# Isolated_UART-USB.net
KiCad netlist of a schematic drawn in Altium Designer
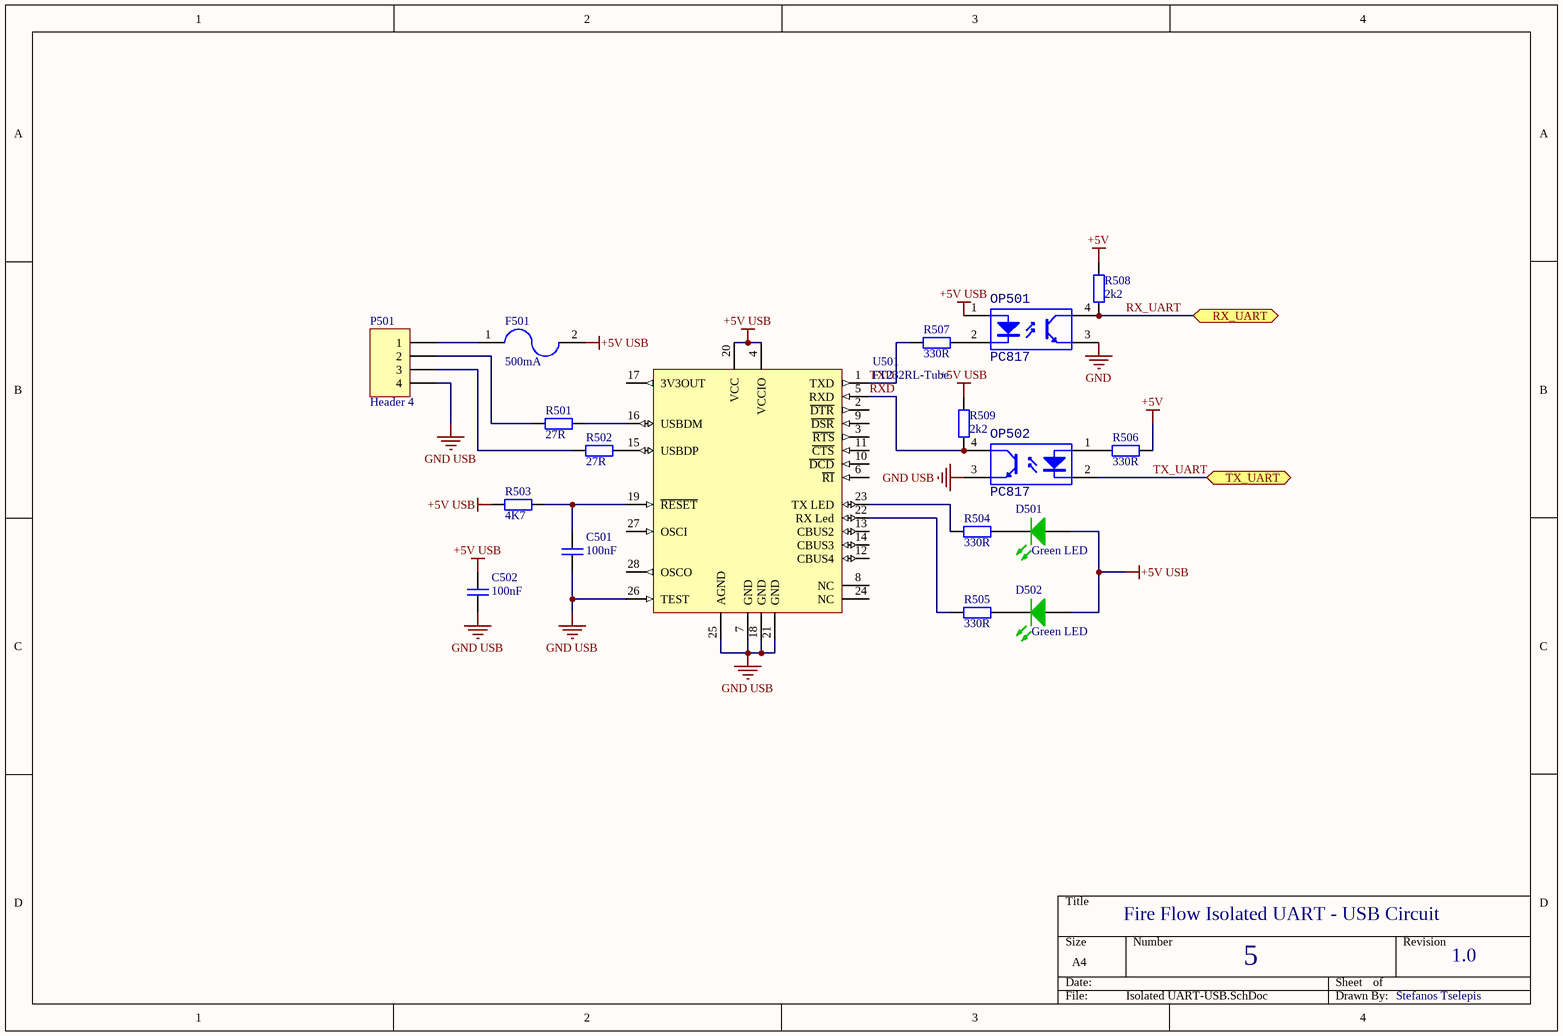
[diagram p0: Isolated UART-USB.SchDoc]

(export (version "E")
  (design (tool "Eeschema 10.0.6"))
  (components
    (comp (ref "C501")
      (value "100nF")
      (footprint "CC2013-0805")
      (libsource (lib "FireFlow Lib") (part "Cap Metal Film"))
    )
    (comp (ref "C502")
      (value "100nF")
      (footprint "CC2013-0805")
      (libsource (lib "FireFlow Lib") (part "Cap Metal Film"))
    )
    (comp (ref "D501")
      (value "Green LED")
      (footprint "CD3216-1206")
      (description "RED")
      (libsource (lib "FireFlow Lib") (part "LED"))
    )
    (comp (ref "D502")
      (value "Green LED")
      (footprint "CD3216-1206")
      (description "RED")
      (libsource (lib "FireFlow Lib") (part "LED"))
    )
    (comp (ref "F501")
      (value "500mA")
      (footprint "CF-1812")
      (description "PPTC")
      (libsource (lib "FireFlow Lib") (part "Fuse"))
    )
    (comp (ref "OP501")
      (value "PC817")
      (footprint "DIP-4")
      (description "DC OPTOCUPLER")
      (libsource (lib "FireFlow") (part "OPTO-DC"))
    )
    (comp (ref "OP502")
      (value "PC817")
      (footprint "DIP-4")
      (description "DC OPTOCUPLER")
      (libsource (lib "FireFlow") (part "OPTO-DC"))
    )
    (comp (ref "P501")
      (value "Header 4")
      (footprint "HDR1X4")
      (description "Header, 4-Pin")
      (fields (field (name "PUBLISHER") "Altium Limited"))
      (libsource (lib "Miscellaneous Connectors") (part "Header 4"))
    )
    (comp (ref "R501") (value "27R") (footprint "CR2012-0805") (libsource (lib "") (part "Resistor_1")))
    (comp (ref "R502") (value "27R") (footprint "CR2012-0805") (libsource (lib "") (part "Resistor_1")))
    (comp (ref "R503")
      (value "4K7")
      (footprint "CR2012-0805")
      (libsource (lib "FireFlow Lib") (part "Resistor"))
    )
    (comp (ref "R504")
      (value "330R")
      (footprint "CR2012-0805")
      (libsource (lib "FireFlow Lib") (part "Resistor"))
    )
    (comp (ref "R505")
      (value "330R")
      (footprint "CR2012-0805")
      (libsource (lib "FireFlow Lib") (part "Resistor"))
    )
    (comp (ref "R506")
      (value "330R")
      (footprint "CR2012-0805")
      (libsource (lib "FireFlow Lib") (part "Resistor"))
    )
    (comp (ref "R507")
      (value "330R")
      (footprint "CR2012-0805")
      (libsource (lib "FireFlow Lib") (part "Resistor"))
    )
    (comp (ref "R508") (value "2k2") (footprint "CR2012-0805") (libsource (lib "") (part "Resistor_2")))
    (comp (ref "R509") (value "2k2") (footprint "CR2012-0805") (libsource (lib "") (part "Resistor_2")))
    (comp (ref "U501")
      (value "FT232RL-Tube")
      (footprint "SSOP-28_N")
      (description "USB UART Asynchronous Serial Data Transfer Chip, SSOP-28, Tube")
      (libsource (lib "FireFlow Lib") (part "FT232RL-Tube"))
    )
  )
  (nets
    (net (code "1") (name "+5V") (class "Default")
      (node (ref "R506") (pin "2") (pinfunction "2_2") (pintype "passive"))
      (node (ref "R508") (pin "2") (pinfunction "2_2") (pintype "passive"))
    )
    (net (code "2") (name "+5V USB") (class "Default")
      (node (ref "C502") (pin "1") (pinfunction "1_1") (pintype "passive"))
      (node (ref "D501") (pin "1") (pinfunction "A_1") (pintype "passive"))
      (node (ref "D502") (pin "1") (pinfunction "A_1") (pintype "passive"))
      (node (ref "F501") (pin "2") (pinfunction "2_2") (pintype "passive"))
      (node (ref "OP501") (pin "1") (pinfunction "A_1") (pintype "passive"))
      (node (ref "R503") (pin "1") (pinfunction "1_1") (pintype "passive"))
      (node (ref "R509") (pin "2") (pinfunction "2_2") (pintype "passive"))
      (node (ref "U501") (pin "20") (pinfunction "VCC_20") (pintype "power_in"))
      (node (ref "U501") (pin "4") (pinfunction "VCCIO_4") (pintype "power_in"))
    )
    (net (code "3") (name "/RXD") (class "Default")
      (node (ref "OP502") (pin "4") (pinfunction "C_4") (pintype "passive"))
      (node (ref "R509") (pin "1") (pinfunction "1_1") (pintype "passive"))
      (node (ref "U501") (pin "5") (pinfunction "RXD_5") (pintype "input"))
    )
    (net (code "4") (name "/RX_UART") (class "Default")
      (node (ref "OP501") (pin "4") (pinfunction "C_4") (pintype "passive"))
      (node (ref "R508") (pin "1") (pinfunction "1_1") (pintype "passive"))
    )
    (net (code "5") (name "/TXD") (class "Default")
      (node (ref "R507") (pin "1") (pinfunction "1_1") (pintype "passive"))
      (node (ref "U501") (pin "1") (pinfunction "TXD_1") (pintype "output"))
    )
    (net (code "6") (name "/TX_UART") (class "Default")
      (node (ref "OP502") (pin "2") (pinfunction "K_2") (pintype "passive"))
    )
    (net (code "7") (name "GND") (class "Default")
      (node (ref "OP501") (pin "3") (pinfunction "E_3") (pintype "passive"))
    )
    (net (code "8") (name "GND USB") (class "Default")
      (node (ref "C501") (pin "2") (pinfunction "2_2") (pintype "passive"))
      (node (ref "C502") (pin "2") (pinfunction "2_2") (pintype "passive"))
      (node (ref "OP502") (pin "3") (pinfunction "E_3") (pintype "passive"))
      (node (ref "P501") (pin "4") (pinfunction "4_4") (pintype "passive"))
      (node (ref "U501") (pin "18") (pinfunction "GND_18") (pintype "power_in"))
      (node (ref "U501") (pin "21") (pinfunction "GND_21") (pintype "power_in"))
      (node (ref "U501") (pin "25") (pinfunction "AGND_25") (pintype "power_in"))
      (node (ref "U501") (pin "26") (pinfunction "TEST_26") (pintype "input"))
      (node (ref "U501") (pin "7") (pinfunction "GND_7") (pintype "power_in"))
    )
    (net (code "9") (name "Net-(D501-K)") (class "Default")
      (node (ref "D501") (pin "2") (pinfunction "K_2") (pintype "passive"))
      (node (ref "R504") (pin "2") (pinfunction "2_2") (pintype "passive"))
    )
    (net (code "10") (name "Net-(D502-K)") (class "Default")
      (node (ref "D502") (pin "2") (pinfunction "K_2") (pintype "passive"))
      (node (ref "R505") (pin "2") (pinfunction "2_2") (pintype "passive"))
    )
    (net (code "11") (name "Net-(F501-Pad1)") (class "Default")
      (node (ref "F501") (pin "1") (pinfunction "1_1") (pintype "passive"))
      (node (ref "P501") (pin "1") (pinfunction "1_1") (pintype "passive"))
    )
    (net (code "12") (name "Net-(OP501-K)") (class "Default")
      (node (ref "OP501") (pin "2") (pinfunction "K_2") (pintype "passive"))
      (node (ref "R507") (pin "2") (pinfunction "2_2") (pintype "passive"))
    )
    (net (code "13") (name "Net-(OP502-A)") (class "Default")
      (node (ref "OP502") (pin "1") (pinfunction "A_1") (pintype "passive"))
      (node (ref "R506") (pin "1") (pinfunction "1_1") (pintype "passive"))
    )
    (net (code "14") (name "Net-(P501-Pad2)") (class "Default")
      (node (ref "P501") (pin "2") (pinfunction "2_2") (pintype "passive"))
      (node (ref "R501") (pin "2") (pinfunction "2_2") (pintype "passive"))
    )
    (net (code "15") (name "Net-(P501-Pad3)") (class "Default")
      (node (ref "P501") (pin "3") (pinfunction "3_3") (pintype "passive"))
      (node (ref "R502") (pin "2") (pinfunction "2_2") (pintype "passive"))
    )
    (net (code "16") (name "Net-(U501-RX_Led)") (class "Default")
      (node (ref "R505") (pin "1") (pinfunction "1_1") (pintype "passive"))
      (node (ref "U501") (pin "22") (pinfunction "RX_Led_22") (pintype "bidirectional"))
    )
    (net (code "17") (name "Net-(U501-TX_LED)") (class "Default")
      (node (ref "R504") (pin "1") (pinfunction "1_1") (pintype "passive"))
      (node (ref "U501") (pin "23") (pinfunction "TX_LED_23") (pintype "bidirectional"))
    )
    (net (code "18") (name "Net-(U501-USBDM)") (class "Default")
      (node (ref "R501") (pin "1") (pinfunction "1_1") (pintype "passive"))
      (node (ref "U501") (pin "16") (pinfunction "USBDM_16") (pintype "bidirectional"))
    )
    (net (code "19") (name "Net-(U501-USBDP)") (class "Default")
      (node (ref "R502") (pin "1") (pinfunction "1_1") (pintype "passive"))
      (node (ref "U501") (pin "15") (pinfunction "USBDP_15") (pintype "bidirectional"))
    )
    (net (code "20") (name "Net-(U501-~{RESET})") (class "Default")
      (node (ref "C501") (pin "1") (pinfunction "1_1") (pintype "passive"))
      (node (ref "R503") (pin "2") (pinfunction "2_2") (pintype "passive"))
      (node (ref "U501") (pin "19") (pinfunction "~{RESET}_19") (pintype "input"))
    )
    (net (code "21") (name "unconnected-(U501-3V3OUT-Pad17)") (class "Default")
      (node (ref "U501") (pin "17") (pinfunction "3V3OUT_17") (pintype "output"))
    )
    (net (code "22") (name "unconnected-(U501-CBUS2-Pad13)") (class "Default")
      (node (ref "U501") (pin "13") (pinfunction "CBUS2_13") (pintype "bidirectional"))
    )
    (net (code "23") (name "unconnected-(U501-CBUS3-Pad14)") (class "Default")
      (node (ref "U501") (pin "14") (pinfunction "CBUS3_14") (pintype "bidirectional"))
    )
    (net (code "24") (name "unconnected-(U501-CBUS4-Pad12)") (class "Default")
      (node (ref "U501") (pin "12") (pinfunction "CBUS4_12") (pintype "bidirectional"))
    )
    (net (code "25") (name "unconnected-(U501-NC-Pad8)") (class "Default")
      (node (ref "U501") (pin "8") (pinfunction "NC_8") (pintype "passive"))
    )
    (net (code "26") (name "unconnected-(U501-NC-Pad24)") (class "Default")
      (node (ref "U501") (pin "24") (pinfunction "NC_24") (pintype "passive"))
    )
    (net (code "27") (name "unconnected-(U501-OSCI-Pad27)") (class "Default")
      (node (ref "U501") (pin "27") (pinfunction "OSCI_27") (pintype "input"))
    )
    (net (code "28") (name "unconnected-(U501-OSCO-Pad28)") (class "Default")
      (node (ref "U501") (pin "28") (pinfunction "OSCO_28") (pintype "output"))
    )
    (net (code "29") (name "unconnected-(U501-~{CTS}-Pad11)") (class "Default")
      (node (ref "U501") (pin "11") (pinfunction "~{CTS}_11") (pintype "input"))
    )
    (net (code "30") (name "unconnected-(U501-~{DCD}-Pad10)") (class "Default")
      (node (ref "U501") (pin "10") (pinfunction "~{DCD}_10") (pintype "input"))
    )
    (net (code "31") (name "unconnected-(U501-~{DSR}-Pad9)") (class "Default")
      (node (ref "U501") (pin "9") (pinfunction "~{DSR}_9") (pintype "input"))
    )
    (net (code "32") (name "unconnected-(U501-~{DTR}-Pad2)") (class "Default")
      (node (ref "U501") (pin "2") (pinfunction "~{DTR}_2") (pintype "output"))
    )
    (net (code "33") (name "unconnected-(U501-~{RI}-Pad6)") (class "Default")
      (node (ref "U501") (pin "6") (pinfunction "~{RI}_6") (pintype "input"))
    )
    (net (code "34") (name "unconnected-(U501-~{RTS}-Pad3)") (class "Default")
      (node (ref "U501") (pin "3") (pinfunction "~{RTS}_3") (pintype "output"))
    )
  )
)
